# picopter_qc.net
KiCad netlist of a schematic drawn in EAGLE
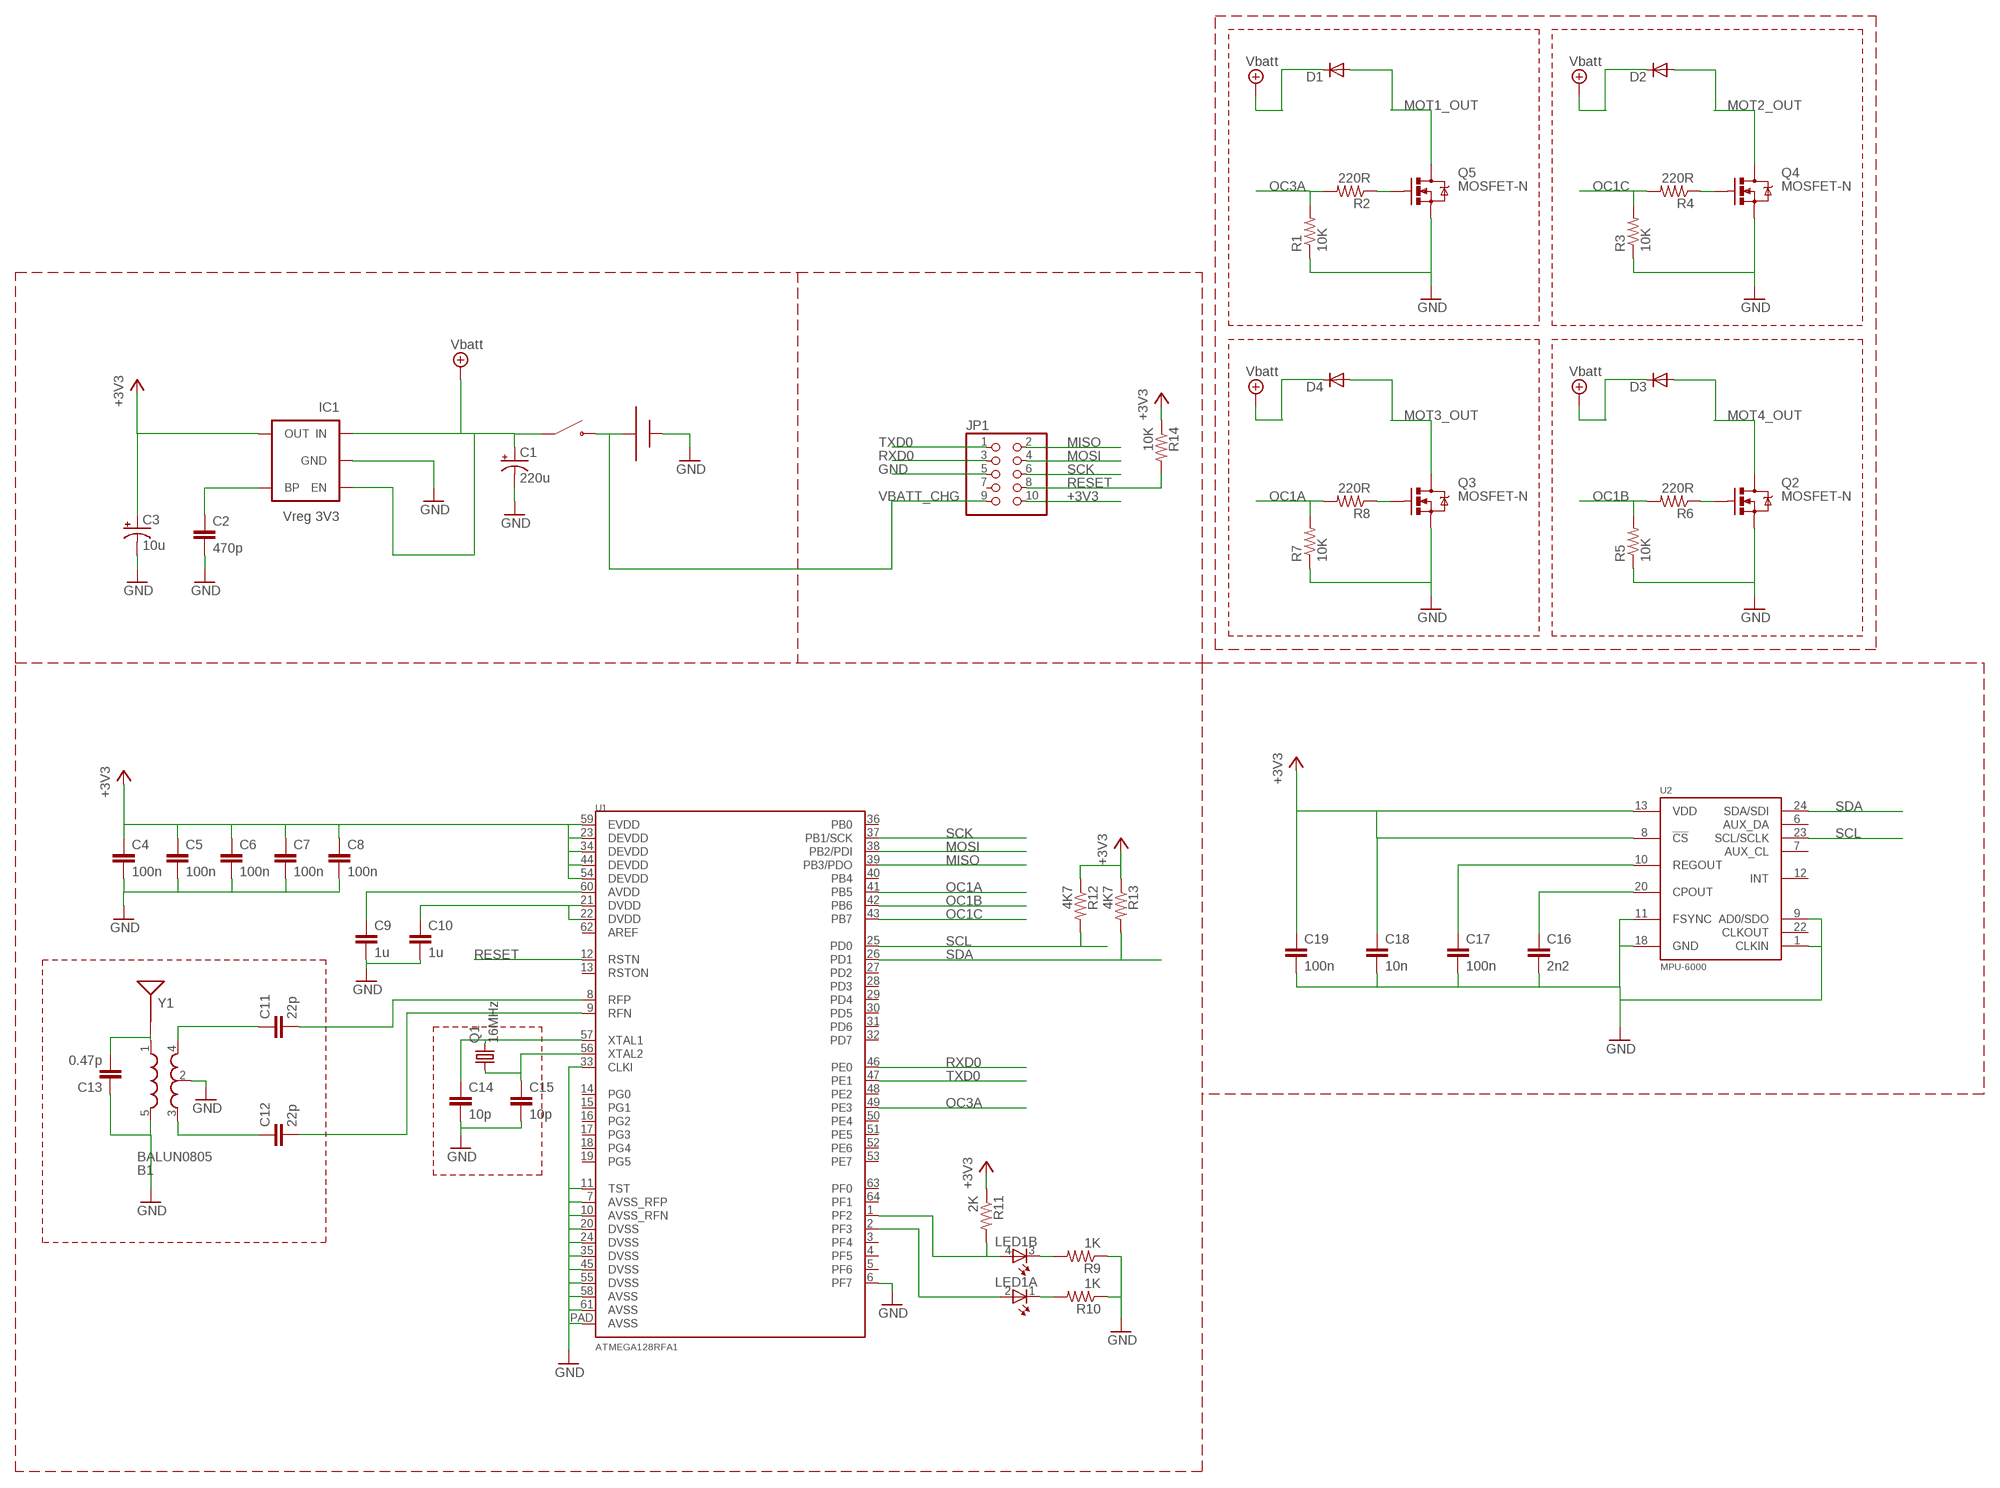
[diagram p0: schematic, sheet 1]

(export (version "E")
  (design (tool "Eeschema 10.0.6"))
  (components
    (comp (ref "B1")
      (value "BALUN0805")
      (footprint "eagle-import:BALUN")
      (libsource (lib "eagle-import") (part "BALUN0805"))
    )
    (comp (ref "BATT1")
      (value "BATT-CONNJST-PH-VERT")
      (footprint "eagle-import:JST-PH-2-VERT")
      (libsource (lib "eagle-import") (part "BATT-CONNJST-PH-VERT"))
    )
    (comp (ref "C1")
      (value "220u")
      (footprint "eagle-import:SMC_B")
      (libsource (lib "eagle-import") (part "CPOL-USSMCB"))
    )
    (comp (ref "C2")
      (value "470p")
      (footprint "eagle-import:C0603")
      (libsource (lib "eagle-import") (part "C-EUC0603"))
    )
    (comp (ref "C3")
      (value "10u")
      (footprint "eagle-import:SMC_B")
      (libsource (lib "eagle-import") (part "CPOL-USSMCB"))
    )
    (comp (ref "C4")
      (value "100n")
      (footprint "eagle-import:C0603")
      (libsource (lib "eagle-import") (part "C-EUC0603"))
    )
    (comp (ref "C5")
      (value "100n")
      (footprint "eagle-import:C0603")
      (libsource (lib "eagle-import") (part "C-EUC0603"))
    )
    (comp (ref "C6")
      (value "100n")
      (footprint "eagle-import:C0603")
      (libsource (lib "eagle-import") (part "C-EUC0603"))
    )
    (comp (ref "C7")
      (value "100n")
      (footprint "eagle-import:C0603")
      (libsource (lib "eagle-import") (part "C-EUC0603"))
    )
    (comp (ref "C8")
      (value "100n")
      (footprint "eagle-import:C0603")
      (libsource (lib "eagle-import") (part "C-EUC0603"))
    )
    (comp (ref "C9")
      (value "1u")
      (footprint "eagle-import:C0603")
      (libsource (lib "eagle-import") (part "C-EUC0603"))
    )
    (comp (ref "C10")
      (value "1u")
      (footprint "eagle-import:C0603")
      (libsource (lib "eagle-import") (part "C-EUC0603"))
    )
    (comp (ref "C11")
      (value "22p")
      (footprint "eagle-import:C0603")
      (libsource (lib "eagle-import") (part "C-EUC0603"))
    )
    (comp (ref "C12")
      (value "22p")
      (footprint "eagle-import:C0603")
      (libsource (lib "eagle-import") (part "C-EUC0603"))
    )
    (comp (ref "C13")
      (value "0.47p")
      (footprint "eagle-import:C0603")
      (libsource (lib "eagle-import") (part "C-EUC0603"))
    )
    (comp (ref "C14")
      (value "10p")
      (footprint "eagle-import:C0603")
      (libsource (lib "eagle-import") (part "C-EUC0603"))
    )
    (comp (ref "C15")
      (value "10p")
      (footprint "eagle-import:C0603")
      (libsource (lib "eagle-import") (part "C-EUC0603"))
    )
    (comp (ref "C16")
      (value "2n2")
      (footprint "eagle-import:C0603")
      (libsource (lib "eagle-import") (part "C-EUC0603"))
    )
    (comp (ref "C17")
      (value "100n")
      (footprint "eagle-import:C0603")
      (libsource (lib "eagle-import") (part "C-EUC0603"))
    )
    (comp (ref "C18")
      (value "10n")
      (footprint "eagle-import:C0603")
      (libsource (lib "eagle-import") (part "C-EUC0603"))
    )
    (comp (ref "C19")
      (value "100n")
      (footprint "eagle-import:C0603")
      (libsource (lib "eagle-import") (part "C-EUC0603"))
    )
    (comp (ref "D1")
      (value "DIODE-MINIMELF")
      (footprint "eagle-import:MINIMELF")
      (libsource (lib "eagle-import") (part "DIODE-MINIMELF"))
    )
    (comp (ref "D2")
      (value "DIODE-MINIMELF")
      (footprint "eagle-import:MINIMELF")
      (libsource (lib "eagle-import") (part "DIODE-MINIMELF"))
    )
    (comp (ref "D3")
      (value "DIODE-MINIMELF")
      (footprint "eagle-import:MINIMELF")
      (libsource (lib "eagle-import") (part "DIODE-MINIMELF"))
    )
    (comp (ref "D4")
      (value "DIODE-MINIMELF")
      (footprint "eagle-import:MINIMELF")
      (libsource (lib "eagle-import") (part "DIODE-MINIMELF"))
    )
    (comp (ref "IC1")
      (value "Vreg 3V3")
      (footprint "eagle-import:SOT23-5")
      (libsource (lib "eagle-import") (part "V_REG_LDOSMD"))
    )
    (comp (ref "JP1")
      (value "PINHD-2X5EDGE")
      (footprint "eagle-import:2X5-EDGE")
      (libsource (lib "eagle-import") (part "PINHD-2X5EDGE"))
    )
    (comp (ref "LED1")
      (value "TOPLED-2-CUSTOM")
      (footprint "eagle-import:TOPLED2CUSTOM")
      (libsource (lib "eagle-import") (part "TOPLED-2-CUSTOM"))
    )
    (comp (ref "Q1")
      (value "16MHz")
      (footprint "eagle-import:CTS406")
      (libsource (lib "eagle-import") (part "CRYSTALCTS406"))
    )
    (comp (ref "Q2")
      (value "MOSFET-N")
      (footprint "eagle-import:SOT23-3")
      (libsource (lib "eagle-import") (part "MOSFET-NCHANNELSMD"))
    )
    (comp (ref "Q3")
      (value "MOSFET-N")
      (footprint "eagle-import:SOT23-3")
      (libsource (lib "eagle-import") (part "MOSFET-NCHANNELSMD"))
    )
    (comp (ref "Q4")
      (value "MOSFET-N")
      (footprint "eagle-import:SOT23-3")
      (libsource (lib "eagle-import") (part "MOSFET-NCHANNELSMD"))
    )
    (comp (ref "Q5")
      (value "MOSFET-N")
      (footprint "eagle-import:SOT23-3")
      (libsource (lib "eagle-import") (part "MOSFET-NCHANNELSMD"))
    )
    (comp (ref "R1")
      (value "10K")
      (footprint "eagle-import:R0603")
      (libsource (lib "eagle-import") (part "R-US_R0603"))
    )
    (comp (ref "R2")
      (value "220R")
      (footprint "eagle-import:R0603")
      (libsource (lib "eagle-import") (part "R-US_R0603"))
    )
    (comp (ref "R3")
      (value "10K")
      (footprint "eagle-import:R0603")
      (libsource (lib "eagle-import") (part "R-US_R0603"))
    )
    (comp (ref "R4")
      (value "220R")
      (footprint "eagle-import:R0603")
      (libsource (lib "eagle-import") (part "R-US_R0603"))
    )
    (comp (ref "R5")
      (value "10K")
      (footprint "eagle-import:R0603")
      (libsource (lib "eagle-import") (part "R-US_R0603"))
    )
    (comp (ref "R6")
      (value "220R")
      (footprint "eagle-import:R0603")
      (libsource (lib "eagle-import") (part "R-US_R0603"))
    )
    (comp (ref "R7")
      (value "10K")
      (footprint "eagle-import:R0603")
      (libsource (lib "eagle-import") (part "R-US_R0603"))
    )
    (comp (ref "R8")
      (value "220R")
      (footprint "eagle-import:R0603")
      (libsource (lib "eagle-import") (part "R-US_R0603"))
    )
    (comp (ref "R9")
      (value "1K")
      (footprint "eagle-import:R0603")
      (libsource (lib "eagle-import") (part "R-US_R0603"))
    )
    (comp (ref "R10")
      (value "1K")
      (footprint "eagle-import:R0603")
      (libsource (lib "eagle-import") (part "R-US_R0603"))
    )
    (comp (ref "R11")
      (value "2K")
      (footprint "eagle-import:R0603")
      (libsource (lib "eagle-import") (part "R-US_R0603"))
    )
    (comp (ref "R12")
      (value "4K7")
      (footprint "eagle-import:R0603")
      (libsource (lib "eagle-import") (part "R-US_R0603"))
    )
    (comp (ref "R13")
      (value "4K7")
      (footprint "eagle-import:R0603")
      (libsource (lib "eagle-import") (part "R-US_R0603"))
    )
    (comp (ref "R14")
      (value "10K")
      (footprint "eagle-import:R0603")
      (libsource (lib "eagle-import") (part "R-US_R0603"))
    )
    (comp (ref "S2")
      (value "SWITCH-PWR-SIMPLE")
      (footprint "eagle-import:SWITCH-PWR")
      (libsource (lib "eagle-import") (part "SWITCH-PWR-SIMPLE"))
    )
    (comp (ref "U1")
      (value "ATMEGA128RFA1")
      (footprint "eagle-import:QFN-64")
      (libsource (lib "eagle-import") (part "ATMEGA128RFA1"))
    )
    (comp (ref "U2")
      (value "MPU-6000")
      (footprint "eagle-import:QFN-24")
      (libsource (lib "eagle-import") (part "MPU-6000"))
    )
    (comp (ref "Y1")
      (value "ANTENNA2SMD5")
      (footprint "eagle-import:ANTENNA-CHIP5")
      (libsource (lib "eagle-import") (part "ANTENNA2SMD5"))
    )
  )
  (nets
    (net (code "1") (name "+3V3") (class "Default")
      (node (ref "C18") (pin "1") (pinfunction "1_1") (pintype "passive"))
      (node (ref "C19") (pin "1") (pinfunction "1_1") (pintype "passive"))
      (node (ref "C3") (pin "+") (pinfunction "+_+") (pintype "passive"))
      (node (ref "C4") (pin "1") (pinfunction "1_1") (pintype "passive"))
      (node (ref "C5") (pin "1") (pinfunction "1_1") (pintype "passive"))
      (node (ref "C6") (pin "1") (pinfunction "1_1") (pintype "passive"))
      (node (ref "C7") (pin "1") (pinfunction "1_1") (pintype "passive"))
      (node (ref "C8") (pin "1") (pinfunction "1_1") (pintype "passive"))
      (node (ref "IC1") (pin "5") (pinfunction "OUT_5") (pintype "passive"))
      (node (ref "JP1") (pin "10") (pinfunction "10_10") (pintype "passive"))
      (node (ref "R11") (pin "1") (pinfunction "1_1") (pintype "passive"))
      (node (ref "R12") (pin "1") (pinfunction "1_1") (pintype "passive"))
      (node (ref "R13") (pin "1") (pinfunction "1_1") (pintype "passive"))
      (node (ref "R14") (pin "1") (pinfunction "1_1") (pintype "passive"))
      (node (ref "U1") (pin "23") (pinfunction "DEVDD_23") (pintype "bidirectional"))
      (node (ref "U1") (pin "34") (pinfunction "DEVDD_34") (pintype "bidirectional"))
      (node (ref "U1") (pin "44") (pinfunction "DEVDD_44") (pintype "bidirectional"))
      (node (ref "U1") (pin "54") (pinfunction "DEVDD_54") (pintype "bidirectional"))
      (node (ref "U1") (pin "59") (pinfunction "EVDD_59") (pintype "bidirectional"))
      (node (ref "U2") (pin "13") (pinfunction "VDD_13") (pintype "bidirectional"))
      (node (ref "U2") (pin "8") (pinfunction "~{CS}_8") (pintype "bidirectional"))
    )
    (net (code "2") (name "/MISO") (class "Default")
      (node (ref "JP1") (pin "2") (pinfunction "2_2") (pintype "passive"))
      (node (ref "U1") (pin "39") (pinfunction "PB3/PDO_39") (pintype "bidirectional"))
    )
    (net (code "3") (name "/MOSI") (class "Default")
      (node (ref "JP1") (pin "4") (pinfunction "4_4") (pintype "passive"))
      (node (ref "U1") (pin "38") (pinfunction "PB2/PDI_38") (pintype "bidirectional"))
    )
    (net (code "4") (name "/MOT1_OUT") (class "Default")
      (node (ref "D1") (pin "A") (pinfunction "A_A") (pintype "passive"))
      (node (ref "Q5") (pin "3") (pinfunction "D_3") (pintype "passive"))
    )
    (net (code "5") (name "/MOT2_OUT") (class "Default")
      (node (ref "D2") (pin "A") (pinfunction "A_A") (pintype "passive"))
      (node (ref "Q4") (pin "3") (pinfunction "D_3") (pintype "passive"))
    )
    (net (code "6") (name "/MOT3_OUT") (class "Default")
      (node (ref "D4") (pin "A") (pinfunction "A_A") (pintype "passive"))
      (node (ref "Q3") (pin "3") (pinfunction "D_3") (pintype "passive"))
    )
    (net (code "7") (name "/MOT4_OUT") (class "Default")
      (node (ref "D3") (pin "A") (pinfunction "A_A") (pintype "passive"))
      (node (ref "Q2") (pin "3") (pinfunction "D_3") (pintype "passive"))
    )
    (net (code "8") (name "/OC1A") (class "Default")
      (node (ref "R7") (pin "2") (pinfunction "2_2") (pintype "passive"))
      (node (ref "R8") (pin "2") (pinfunction "2_2") (pintype "passive"))
      (node (ref "U1") (pin "41") (pinfunction "PB5_41") (pintype "bidirectional"))
    )
    (net (code "9") (name "/OC1B") (class "Default")
      (node (ref "R5") (pin "2") (pinfunction "2_2") (pintype "passive"))
      (node (ref "R6") (pin "2") (pinfunction "2_2") (pintype "passive"))
      (node (ref "U1") (pin "42") (pinfunction "PB6_42") (pintype "bidirectional"))
    )
    (net (code "10") (name "/OC1C") (class "Default")
      (node (ref "R3") (pin "2") (pinfunction "2_2") (pintype "passive"))
      (node (ref "R4") (pin "2") (pinfunction "2_2") (pintype "passive"))
      (node (ref "U1") (pin "43") (pinfunction "PB7_43") (pintype "bidirectional"))
    )
    (net (code "11") (name "/OC3A") (class "Default")
      (node (ref "R1") (pin "2") (pinfunction "2_2") (pintype "passive"))
      (node (ref "R2") (pin "2") (pinfunction "2_2") (pintype "passive"))
      (node (ref "U1") (pin "49") (pinfunction "PE3_49") (pintype "bidirectional"))
    )
    (net (code "12") (name "/RESET") (class "Default")
      (node (ref "JP1") (pin "8") (pinfunction "8_8") (pintype "passive"))
      (node (ref "R14") (pin "2") (pinfunction "2_2") (pintype "passive"))
      (node (ref "U1") (pin "12") (pinfunction "RSTN_12") (pintype "bidirectional"))
    )
    (net (code "13") (name "/RXD0") (class "Default")
      (node (ref "JP1") (pin "3") (pinfunction "3_3") (pintype "passive"))
      (node (ref "U1") (pin "46") (pinfunction "PE0_46") (pintype "bidirectional"))
    )
    (net (code "14") (name "/SCK") (class "Default")
      (node (ref "JP1") (pin "6") (pinfunction "6_6") (pintype "passive"))
      (node (ref "U1") (pin "37") (pinfunction "PB1/SCK_37") (pintype "bidirectional"))
    )
    (net (code "15") (name "/SCL") (class "Default")
      (node (ref "R12") (pin "2") (pinfunction "2_2") (pintype "passive"))
      (node (ref "U1") (pin "25") (pinfunction "PD0_25") (pintype "bidirectional"))
      (node (ref "U2") (pin "23") (pinfunction "SCL/SCLK_23") (pintype "bidirectional"))
    )
    (net (code "16") (name "/SDA") (class "Default")
      (node (ref "R13") (pin "2") (pinfunction "2_2") (pintype "passive"))
      (node (ref "U1") (pin "26") (pinfunction "PD1_26") (pintype "bidirectional"))
      (node (ref "U2") (pin "24") (pinfunction "SDA/SDI_24") (pintype "bidirectional"))
    )
    (net (code "17") (name "/TXD0") (class "Default")
      (node (ref "JP1") (pin "1") (pinfunction "1_1") (pintype "passive"))
      (node (ref "U1") (pin "47") (pinfunction "PE1_47") (pintype "bidirectional"))
    )
    (net (code "18") (name "/VBATT_CHG") (class "Default")
      (node (ref "BATT1") (pin "P") (pinfunction "P_P") (pintype "power_in"))
      (node (ref "JP1") (pin "9") (pinfunction "9_9") (pintype "passive"))
      (node (ref "S2") (pin "P$2") (pinfunction "P$2_P$2") (pintype "passive"))
    )
    (net (code "19") (name "GND") (class "Default")
      (node (ref "B1") (pin "2") (pinfunction "GND_2") (pintype "bidirectional"))
      (node (ref "B1") (pin "5") (pinfunction "GND_5") (pintype "bidirectional"))
      (node (ref "BATT1") (pin "N") (pinfunction "N_N") (pintype "power_in"))
      (node (ref "C1") (pin "-") (pinfunction "-_-") (pintype "passive"))
      (node (ref "C10") (pin "2") (pinfunction "2_2") (pintype "passive"))
      (node (ref "C13") (pin "1") (pinfunction "1_1") (pintype "passive"))
      (node (ref "C14") (pin "2") (pinfunction "2_2") (pintype "passive"))
      (node (ref "C15") (pin "2") (pinfunction "2_2") (pintype "passive"))
      (node (ref "C16") (pin "2") (pinfunction "2_2") (pintype "passive"))
      (node (ref "C17") (pin "2") (pinfunction "2_2") (pintype "passive"))
      (node (ref "C18") (pin "2") (pinfunction "2_2") (pintype "passive"))
      (node (ref "C19") (pin "2") (pinfunction "2_2") (pintype "passive"))
      (node (ref "C2") (pin "2") (pinfunction "2_2") (pintype "passive"))
      (node (ref "C3") (pin "-") (pinfunction "-_-") (pintype "passive"))
      (node (ref "C4") (pin "2") (pinfunction "2_2") (pintype "passive"))
      (node (ref "C5") (pin "2") (pinfunction "2_2") (pintype "passive"))
      (node (ref "C6") (pin "2") (pinfunction "2_2") (pintype "passive"))
      (node (ref "C7") (pin "2") (pinfunction "2_2") (pintype "passive"))
      (node (ref "C8") (pin "2") (pinfunction "2_2") (pintype "passive"))
      (node (ref "C9") (pin "2") (pinfunction "2_2") (pintype "passive"))
      (node (ref "IC1") (pin "2") (pinfunction "GND_2") (pintype "input"))
      (node (ref "JP1") (pin "5") (pinfunction "5_5") (pintype "passive"))
      (node (ref "Q2") (pin "2") (pinfunction "S_2") (pintype "passive"))
      (node (ref "Q3") (pin "2") (pinfunction "S_2") (pintype "passive"))
      (node (ref "Q4") (pin "2") (pinfunction "S_2") (pintype "passive"))
      (node (ref "Q5") (pin "2") (pinfunction "S_2") (pintype "passive"))
      (node (ref "R1") (pin "1") (pinfunction "1_1") (pintype "passive"))
      (node (ref "R10") (pin "1") (pinfunction "1_1") (pintype "passive"))
      (node (ref "R3") (pin "1") (pinfunction "1_1") (pintype "passive"))
      (node (ref "R5") (pin "1") (pinfunction "1_1") (pintype "passive"))
      (node (ref "R7") (pin "1") (pinfunction "1_1") (pintype "passive"))
      (node (ref "R9") (pin "1") (pinfunction "1_1") (pintype "passive"))
      (node (ref "U1") (pin "10") (pinfunction "AVSS_RFN_10") (pintype "bidirectional"))
      (node (ref "U1") (pin "11") (pinfunction "TST_11") (pintype "bidirectional"))
      (node (ref "U1") (pin "20") (pinfunction "DVSS_20") (pintype "bidirectional"))
      (node (ref "U1") (pin "24") (pinfunction "DVSS_24") (pintype "bidirectional"))
      (node (ref "U1") (pin "33") (pinfunction "CLKI_33") (pintype "bidirectional"))
      (node (ref "U1") (pin "35") (pinfunction "DVSS_35") (pintype "bidirectional"))
      (node (ref "U1") (pin "45") (pinfunction "DVSS_45") (pintype "bidirectional"))
      (node (ref "U1") (pin "55") (pinfunction "DVSS_55") (pintype "bidirectional"))
      (node (ref "U1") (pin "58") (pinfunction "AVSS_58") (pintype "bidirectional"))
      (node (ref "U1") (pin "6") (pinfunction "PF7_6") (pintype "bidirectional"))
      (node (ref "U1") (pin "61") (pinfunction "AVSS_61") (pintype "bidirectional"))
      (node (ref "U1") (pin "7") (pinfunction "AVSS_RFP_7") (pintype "bidirectional"))
      (node (ref "U1") (pin "PAD") (pinfunction "AVSS_PAD") (pintype "bidirectional"))
      (node (ref "U2") (pin "1") (pinfunction "CLKIN_1") (pintype "bidirectional"))
      (node (ref "U2") (pin "11") (pinfunction "FSYNC_11") (pintype "bidirectional"))
      (node (ref "U2") (pin "18") (pinfunction "GND_18") (pintype "bidirectional"))
      (node (ref "U2") (pin "9") (pinfunction "AD0/SDO_9") (pintype "bidirectional"))
    )
    (net (code "20") (name "Net-(B1-IN)") (class "Default")
      (node (ref "B1") (pin "1") (pinfunction "IN_1") (pintype "bidirectional"))
      (node (ref "C13") (pin "2") (pinfunction "2_2") (pintype "passive"))
      (node (ref "Y1") (pin "FEED") (pinfunction "SIGNAL_FEED") (pintype "bidirectional"))
    )
    (net (code "21") (name "Net-(B1-OUT1)") (class "Default")
      (node (ref "B1") (pin "3") (pinfunction "OUT1_3") (pintype "bidirectional"))
      (node (ref "C12") (pin "1") (pinfunction "1_1") (pintype "passive"))
    )
    (net (code "22") (name "Net-(B1-OUT2)") (class "Default")
      (node (ref "B1") (pin "4") (pinfunction "OUT2_4") (pintype "bidirectional"))
      (node (ref "C11") (pin "1") (pinfunction "1_1") (pintype "passive"))
    )
    (net (code "23") (name "Net-(C10-Pad1)") (class "Default")
      (node (ref "C10") (pin "1") (pinfunction "1_1") (pintype "passive"))
      (node (ref "U1") (pin "21") (pinfunction "DVDD_21") (pintype "bidirectional"))
      (node (ref "U1") (pin "22") (pinfunction "DVDD_22") (pintype "bidirectional"))
    )
    (net (code "24") (name "Net-(IC1-BP)") (class "Default")
      (node (ref "C2") (pin "1") (pinfunction "1_1") (pintype "passive"))
      (node (ref "IC1") (pin "4") (pinfunction "BP_4") (pintype "input"))
    )
    (net (code "25") (name "Net-(LED1A-A)") (class "Default")
      (node (ref "LED1") (pin "2") (pinfunction "A_2") (pintype "passive"))
      (node (ref "U1") (pin "2") (pinfunction "PF3_2") (pintype "bidirectional"))
    )
    (net (code "26") (name "Net-(LED1A-C)") (class "Default")
      (node (ref "LED1") (pin "1") (pinfunction "C_1") (pintype "passive"))
      (node (ref "R10") (pin "2") (pinfunction "2_2") (pintype "passive"))
    )
    (net (code "27") (name "Net-(LED1B-A)") (class "Default")
      (node (ref "LED1") (pin "4") (pinfunction "A_4") (pintype "passive"))
      (node (ref "R11") (pin "2") (pinfunction "2_2") (pintype "passive"))
      (node (ref "U1") (pin "1") (pinfunction "PF2_1") (pintype "bidirectional"))
    )
    (net (code "28") (name "Net-(LED1B-C)") (class "Default")
      (node (ref "LED1") (pin "3") (pinfunction "C_3") (pintype "passive"))
      (node (ref "R9") (pin "2") (pinfunction "2_2") (pintype "passive"))
    )
    (net (code "29") (name "Net-(Q1-2)") (class "Default")
      (node (ref "C14") (pin "1") (pinfunction "1_1") (pintype "passive"))
      (node (ref "Q1") (pin "3") (pinfunction "2_3") (pintype "passive"))
      (node (ref "U1") (pin "57") (pinfunction "XTAL1_57") (pintype "bidirectional"))
    )
    (net (code "30") (name "Net-(Q2-G)") (class "Default")
      (node (ref "Q2") (pin "1") (pinfunction "G_1") (pintype "passive"))
      (node (ref "R6") (pin "1") (pinfunction "1_1") (pintype "passive"))
    )
    (net (code "31") (name "Net-(Q3-G)") (class "Default")
      (node (ref "Q3") (pin "1") (pinfunction "G_1") (pintype "passive"))
      (node (ref "R8") (pin "1") (pinfunction "1_1") (pintype "passive"))
    )
    (net (code "32") (name "Net-(Q4-G)") (class "Default")
      (node (ref "Q4") (pin "1") (pinfunction "G_1") (pintype "passive"))
      (node (ref "R4") (pin "1") (pinfunction "1_1") (pintype "passive"))
    )
    (net (code "33") (name "Net-(Q5-G)") (class "Default")
      (node (ref "Q5") (pin "1") (pinfunction "G_1") (pintype "passive"))
      (node (ref "R2") (pin "1") (pinfunction "1_1") (pintype "passive"))
    )
    (net (code "34") (name "Net-(U1-AVDD)") (class "Default")
      (node (ref "C9") (pin "1") (pinfunction "1_1") (pintype "passive"))
      (node (ref "U1") (pin "60") (pinfunction "AVDD_60") (pintype "bidirectional"))
    )
    (net (code "35") (name "Net-(U1-RFN)") (class "Default")
      (node (ref "C12") (pin "2") (pinfunction "2_2") (pintype "passive"))
      (node (ref "U1") (pin "9") (pinfunction "RFN_9") (pintype "bidirectional"))
    )
    (net (code "36") (name "Net-(U1-RFP)") (class "Default")
      (node (ref "C11") (pin "2") (pinfunction "2_2") (pintype "passive"))
      (node (ref "U1") (pin "8") (pinfunction "RFP_8") (pintype "bidirectional"))
    )
    (net (code "37") (name "Net-(U1-XTAL2)") (class "Default")
      (node (ref "C15") (pin "1") (pinfunction "1_1") (pintype "passive"))
      (node (ref "Q1") (pin "1") (pinfunction "1_1") (pintype "passive"))
      (node (ref "U1") (pin "56") (pinfunction "XTAL2_56") (pintype "bidirectional"))
    )
    (net (code "38") (name "Net-(U2-CPOUT)") (class "Default")
      (node (ref "C16") (pin "1") (pinfunction "1_1") (pintype "passive"))
      (node (ref "U2") (pin "20") (pinfunction "CPOUT_20") (pintype "bidirectional"))
    )
    (net (code "39") (name "Net-(U2-REGOUT)") (class "Default")
      (node (ref "C17") (pin "1") (pinfunction "1_1") (pintype "passive"))
      (node (ref "U2") (pin "10") (pinfunction "REGOUT_10") (pintype "bidirectional"))
    )
    (net (code "40") (name "Vbatt") (class "Default")
      (node (ref "C1") (pin "+") (pinfunction "+_+") (pintype "passive"))
      (node (ref "D1") (pin "C") (pinfunction "C_C") (pintype "passive"))
      (node (ref "D2") (pin "C") (pinfunction "C_C") (pintype "passive"))
      (node (ref "D3") (pin "C") (pinfunction "C_C") (pintype "passive"))
      (node (ref "D4") (pin "C") (pinfunction "C_C") (pintype "passive"))
      (node (ref "IC1") (pin "1") (pinfunction "IN_1") (pintype "input"))
      (node (ref "IC1") (pin "3") (pinfunction "EN_3") (pintype "input"))
      (node (ref "S2") (pin "P$1") (pinfunction "P$1_P$1") (pintype "passive"))
    )
    (net (code "41") (name "unconnected-(JP1-Pad7)") (class "Default")
      (node (ref "JP1") (pin "7") (pinfunction "7_7") (pintype "passive"))
    )
    (net (code "42") (name "unconnected-(U1-AREF-Pad62)") (class "Default")
      (node (ref "U1") (pin "62") (pinfunction "AREF_62") (pintype "bidirectional"))
    )
    (net (code "43") (name "unconnected-(U1-PB0-Pad36)") (class "Default")
      (node (ref "U1") (pin "36") (pinfunction "PB0_36") (pintype "bidirectional"))
    )
    (net (code "44") (name "unconnected-(U1-PB4-Pad40)") (class "Default")
      (node (ref "U1") (pin "40") (pinfunction "PB4_40") (pintype "bidirectional"))
    )
    (net (code "45") (name "unconnected-(U1-PD2-Pad27)") (class "Default")
      (node (ref "U1") (pin "27") (pinfunction "PD2_27") (pintype "bidirectional"))
    )
    (net (code "46") (name "unconnected-(U1-PD3-Pad28)") (class "Default")
      (node (ref "U1") (pin "28") (pinfunction "PD3_28") (pintype "bidirectional"))
    )
    (net (code "47") (name "unconnected-(U1-PD4-Pad29)") (class "Default")
      (node (ref "U1") (pin "29") (pinfunction "PD4_29") (pintype "bidirectional"))
    )
    (net (code "48") (name "unconnected-(U1-PD5-Pad30)") (class "Default")
      (node (ref "U1") (pin "30") (pinfunction "PD5_30") (pintype "bidirectional"))
    )
    (net (code "49") (name "unconnected-(U1-PD6-Pad31)") (class "Default")
      (node (ref "U1") (pin "31") (pinfunction "PD6_31") (pintype "bidirectional"))
    )
    (net (code "50") (name "unconnected-(U1-PD7-Pad32)") (class "Default")
      (node (ref "U1") (pin "32") (pinfunction "PD7_32") (pintype "bidirectional"))
    )
    (net (code "51") (name "unconnected-(U1-PE2-Pad48)") (class "Default")
      (node (ref "U1") (pin "48") (pinfunction "PE2_48") (pintype "bidirectional"))
    )
    (net (code "52") (name "unconnected-(U1-PE4-Pad50)") (class "Default")
      (node (ref "U1") (pin "50") (pinfunction "PE4_50") (pintype "bidirectional"))
    )
    (net (code "53") (name "unconnected-(U1-PE5-Pad51)") (class "Default")
      (node (ref "U1") (pin "51") (pinfunction "PE5_51") (pintype "bidirectional"))
    )
    (net (code "54") (name "unconnected-(U1-PE6-Pad52)") (class "Default")
      (node (ref "U1") (pin "52") (pinfunction "PE6_52") (pintype "bidirectional"))
    )
    (net (code "55") (name "unconnected-(U1-PE7-Pad53)") (class "Default")
      (node (ref "U1") (pin "53") (pinfunction "PE7_53") (pintype "bidirectional"))
    )
    (net (code "56") (name "unconnected-(U1-PF0-Pad63)") (class "Default")
      (node (ref "U1") (pin "63") (pinfunction "PF0_63") (pintype "bidirectional"))
    )
    (net (code "57") (name "unconnected-(U1-PF1-Pad64)") (class "Default")
      (node (ref "U1") (pin "64") (pinfunction "PF1_64") (pintype "bidirectional"))
    )
    (net (code "58") (name "unconnected-(U1-PF4-Pad3)") (class "Default")
      (node (ref "U1") (pin "3") (pinfunction "PF4_3") (pintype "bidirectional"))
    )
    (net (code "59") (name "unconnected-(U1-PF5-Pad4)") (class "Default")
      (node (ref "U1") (pin "4") (pinfunction "PF5_4") (pintype "bidirectional"))
    )
    (net (code "60") (name "unconnected-(U1-PF6-Pad5)") (class "Default")
      (node (ref "U1") (pin "5") (pinfunction "PF6_5") (pintype "bidirectional"))
    )
    (net (code "61") (name "unconnected-(U1-PG0-Pad14)") (class "Default")
      (node (ref "U1") (pin "14") (pinfunction "PG0_14") (pintype "bidirectional"))
    )
    (net (code "62") (name "unconnected-(U1-PG1-Pad15)") (class "Default")
      (node (ref "U1") (pin "15") (pinfunction "PG1_15") (pintype "bidirectional"))
    )
    (net (code "63") (name "unconnected-(U1-PG2-Pad16)") (class "Default")
      (node (ref "U1") (pin "16") (pinfunction "PG2_16") (pintype "bidirectional"))
    )
    (net (code "64") (name "unconnected-(U1-PG3-Pad17)") (class "Default")
      (node (ref "U1") (pin "17") (pinfunction "PG3_17") (pintype "bidirectional"))
    )
    (net (code "65") (name "unconnected-(U1-PG4-Pad18)") (class "Default")
      (node (ref "U1") (pin "18") (pinfunction "PG4_18") (pintype "bidirectional"))
    )
    (net (code "66") (name "unconnected-(U1-PG5-Pad19)") (class "Default")
      (node (ref "U1") (pin "19") (pinfunction "PG5_19") (pintype "bidirectional"))
    )
    (net (code "67") (name "unconnected-(U1-RSTON-Pad13)") (class "Default")
      (node (ref "U1") (pin "13") (pinfunction "RSTON_13") (pintype "bidirectional"))
    )
    (net (code "68") (name "unconnected-(U2-AUX_CL-Pad7)") (class "Default")
      (node (ref "U2") (pin "7") (pinfunction "AUX_CL_7") (pintype "bidirectional"))
    )
    (net (code "69") (name "unconnected-(U2-AUX_DA-Pad6)") (class "Default")
      (node (ref "U2") (pin "6") (pinfunction "AUX_DA_6") (pintype "bidirectional"))
    )
    (net (code "70") (name "unconnected-(U2-CLKOUT-Pad22)") (class "Default")
      (node (ref "U2") (pin "22") (pinfunction "CLKOUT_22") (pintype "bidirectional"))
    )
    (net (code "71") (name "unconnected-(U2-INT-Pad12)") (class "Default")
      (node (ref "U2") (pin "12") (pinfunction "INT_12") (pintype "bidirectional"))
    )
  )
)
